# Main.net
KiCad netlist of a schematic drawn in EAGLE
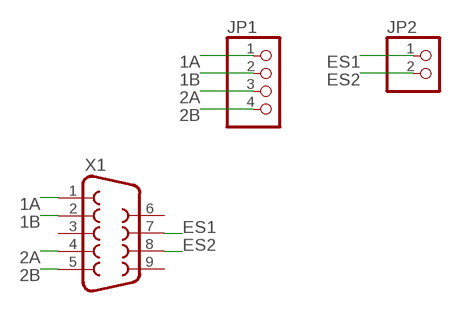
[diagram p0: schematic, sheet 1]

(export (version "E")
  (design (tool "Eeschema 10.0.6"))
  (components
    (comp (ref "JP1")
      (value "PINHD-1X4")
      (footprint "eagle-import:1X04")
      (libsource (lib "eagle-import") (part "PINHD-1X4"))
    )
    (comp (ref "JP2")
      (value "PINHD-1X2")
      (footprint "eagle-import:1X02")
      (libsource (lib "eagle-import") (part "PINHD-1X2"))
    )
    (comp (ref "X1")
      (value "F09HP")
      (footprint "eagle-import:F09HP")
      (libsource (lib "eagle-import") (part "F09HP"))
    )
  )
  (nets
    (net (code "1") (name "/1A") (class "Default")
      (node (ref "JP1") (pin "1") (pinfunction "1_1") (pintype "passive"))
      (node (ref "X1") (pin "1") (pinfunction "1_1") (pintype "passive"))
    )
    (net (code "2") (name "/1B") (class "Default")
      (node (ref "JP1") (pin "2") (pinfunction "2_2") (pintype "passive"))
      (node (ref "X1") (pin "2") (pinfunction "2_2") (pintype "passive"))
    )
    (net (code "3") (name "/2A") (class "Default")
      (node (ref "JP1") (pin "3") (pinfunction "3_3") (pintype "passive"))
      (node (ref "X1") (pin "4") (pinfunction "4_4") (pintype "passive"))
    )
    (net (code "4") (name "/2B") (class "Default")
      (node (ref "JP1") (pin "4") (pinfunction "4_4") (pintype "passive"))
      (node (ref "X1") (pin "5") (pinfunction "5_5") (pintype "passive"))
    )
    (net (code "5") (name "/ES1") (class "Default")
      (node (ref "JP2") (pin "1") (pinfunction "1_1") (pintype "passive"))
      (node (ref "X1") (pin "7") (pinfunction "7_7") (pintype "passive"))
    )
    (net (code "6") (name "/ES2") (class "Default")
      (node (ref "JP2") (pin "2") (pinfunction "2_2") (pintype "passive"))
      (node (ref "X1") (pin "8") (pinfunction "8_8") (pintype "passive"))
    )
    (net (code "7") (name "unconnected-(X1-Pad3)") (class "Default")
      (node (ref "X1") (pin "3") (pinfunction "3_3") (pintype "passive"))
    )
    (net (code "8") (name "unconnected-(X1-Pad6)") (class "Default")
      (node (ref "X1") (pin "6") (pinfunction "6_6") (pintype "passive"))
    )
    (net (code "9") (name "unconnected-(X1-Pad9)") (class "Default")
      (node (ref "X1") (pin "9") (pinfunction "9_9") (pintype "passive"))
    )
  )
)
